# CanController.net
KiCad netlist of a schematic drawn in Altium Designer
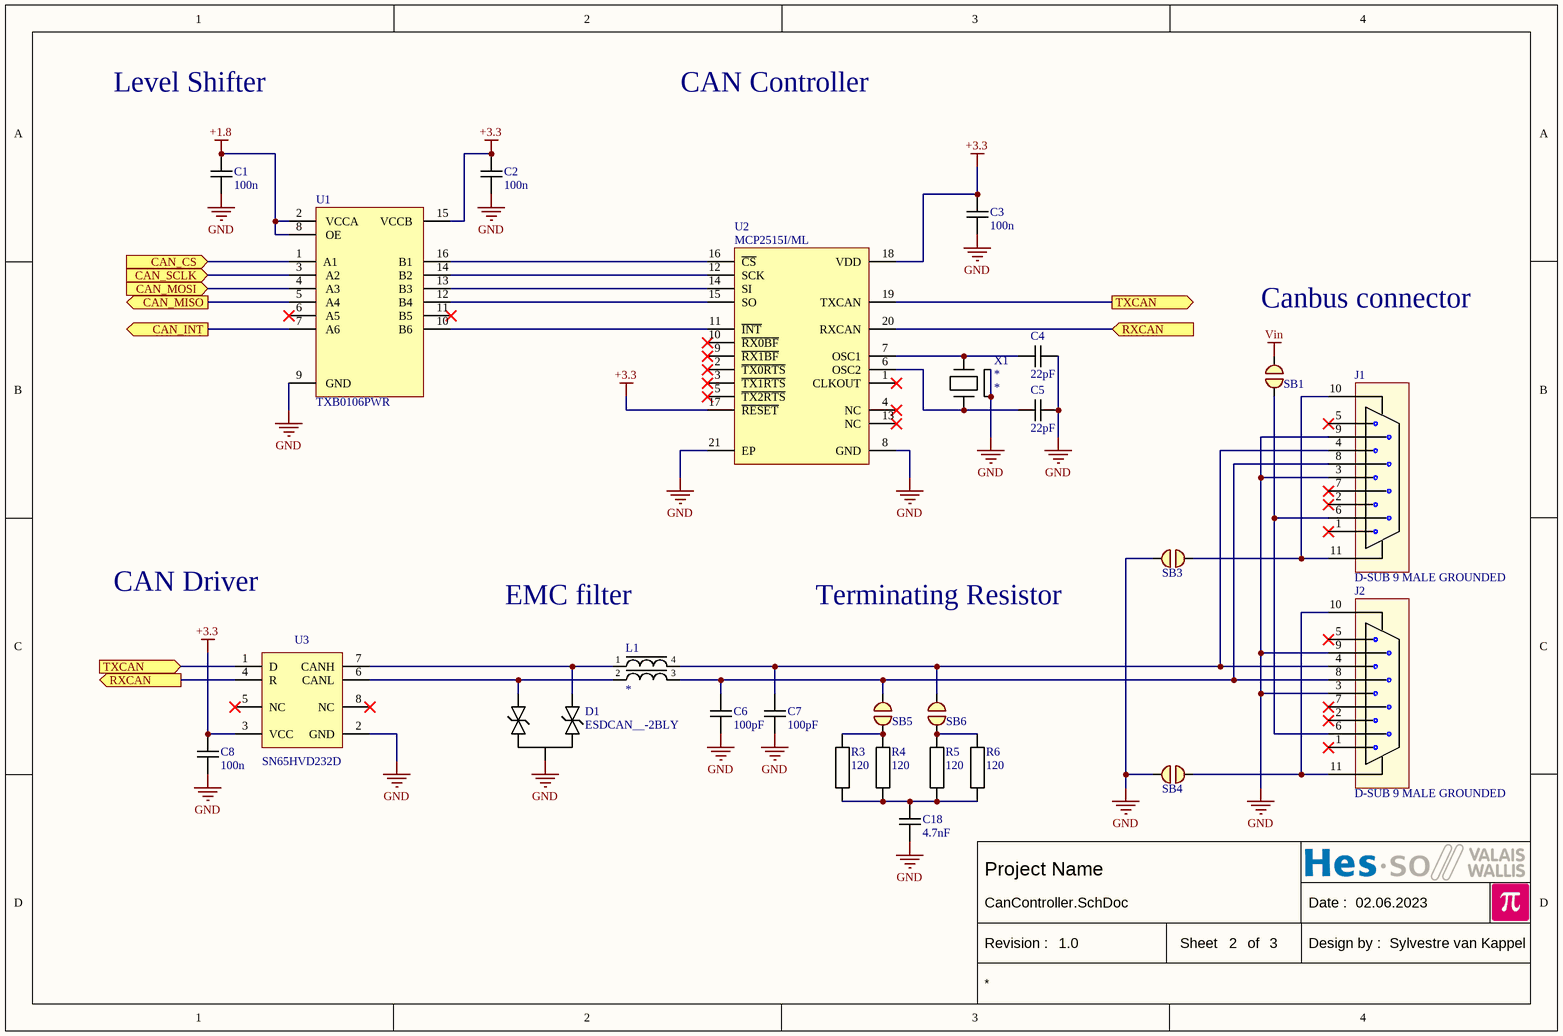
[diagram p0: CanController.SchDoc]

(export (version "E")
  (design (tool "Eeschema 10.0.6"))
  (components
    (comp (ref "C1")
      (value "100n")
      (footprint "CAPACITOR 1608 REFLOW")
      (description "Capacitor")
      (libsource (lib "Capacitor") (part "Capacitor"))
    )
    (comp (ref "C2")
      (value "100n")
      (footprint "CAPACITOR 1608 REFLOW")
      (description "Capacitor")
      (libsource (lib "Capacitor") (part "Capacitor"))
    )
    (comp (ref "C3")
      (value "100n")
      (footprint "CAPACITOR 1608 REFLOW")
      (description "Capacitor")
      (libsource (lib "Capacitor") (part "Capacitor"))
    )
    (comp (ref "C4")
      (value "22pF")
      (footprint "CAPACITOR 1608 REFLOW")
      (description "Capacitor")
      (libsource (lib "Capacitor") (part "Capacitor"))
    )
    (comp (ref "C5")
      (value "22pF")
      (footprint "CAPACITOR 1608 REFLOW")
      (description "Capacitor")
      (libsource (lib "Capacitor") (part "Capacitor"))
    )
    (comp (ref "C6")
      (value "100pF")
      (footprint "CAPACITOR 1608 REFLOW")
      (description "Capacitor")
      (libsource (lib "Capacitor") (part "Capacitor"))
    )
    (comp (ref "C7")
      (value "100pF")
      (footprint "CAPACITOR 1608 REFLOW")
      (description "Capacitor")
      (libsource (lib "Capacitor") (part "Capacitor"))
    )
    (comp (ref "C8")
      (value "100n")
      (footprint "CAPACITOR 1608 REFLOW")
      (description "Capacitor")
      (libsource (lib "Capacitor") (part "Capacitor"))
    )
    (comp (ref "C18")
      (value "4.7nF")
      (footprint "CAPACITOR 1608 REFLOW")
      (description "Capacitor")
      (libsource (lib "Capacitor") (part "Capacitor"))
    )
    (comp (ref "D1")
      (value "ESDCAN__-2BLY")
      (footprint "SOT23 P0.95 C1.6x3.0 H1.3")
      (description "Automotive dual-line TVS diode")
      (libsource (lib "Diode") (part "Diode ESDCAN__-2BLY"))
    )
    (comp (ref "J1")
      (value "D-SUB 9 MALE GROUNDED")
      (footprint "D-SUB 9 MALE ANGLE")
      (description "D-Subminiature 9 way Plug Right Angle")
      (libsource (lib "Connector") (part "D-SUB 9 MALE GROUNDED"))
    )
    (comp (ref "J2")
      (value "D-SUB 9 MALE GROUNDED")
      (footprint "D-SUB 9 MALE ANGLE")
      (description "D-Subminiature 9 way Plug Right Angle")
      (libsource (lib "Connector") (part "D-SUB 9 MALE GROUNDED"))
    )
    (comp (ref "L1")
      (value "*")
      (footprint "L CM 2X B82793C EPCOS")
      (description "Inductor Common Mode Filter")
      (libsource (lib "Inductor") (part "L CM 2X B82793C0 EPCOS"))
    )
    (comp (ref "R3")
      (value "120")
      (footprint "RESISTOR 1608 REFLOW")
      (description "Resistor")
      (libsource (lib "Resistor") (part "Resistor"))
    )
    (comp (ref "R4")
      (value "120")
      (footprint "RESISTOR 1608 REFLOW")
      (description "Resistor")
      (libsource (lib "Resistor") (part "Resistor"))
    )
    (comp (ref "R5")
      (value "120")
      (footprint "RESISTOR 1608 REFLOW")
      (description "Resistor")
      (libsource (lib "Resistor") (part "Resistor"))
    )
    (comp (ref "R6")
      (value "120")
      (footprint "RESISTOR 1608 REFLOW")
      (description "Resistor")
      (libsource (lib "Resistor") (part "Resistor"))
    )
    (comp (ref "SB1")
      (value "*")
      (footprint "Solder Bridge 1mm Unconnected")
      (description "Solderbridge Unconnected")
      (libsource (lib "Jumper") (part "Solderbridge Unconnected"))
    )
    (comp (ref "SB3")
      (value "*")
      (footprint "Solder Bridge 1mm Unconnected")
      (description "Solderbridge Unconnected")
      (libsource (lib "Jumper") (part "Solderbridge Unconnected"))
    )
    (comp (ref "SB4")
      (value "*")
      (footprint "Solder Bridge 1mm Unconnected")
      (description "Solderbridge Unconnected")
      (libsource (lib "Jumper") (part "Solderbridge Unconnected"))
    )
    (comp (ref "SB5")
      (value "*")
      (footprint "Solder Bridge 1mm Unconnected")
      (description "Solderbridge Unconnected")
      (libsource (lib "Jumper") (part "Solderbridge Unconnected"))
    )
    (comp (ref "SB6")
      (value "*")
      (footprint "Solder Bridge 1mm Unconnected")
      (description "Solderbridge Unconnected")
      (libsource (lib "Jumper") (part "Solderbridge Unconnected"))
    )
    (comp (ref "U1")
      (value "TXB0106PWR")
      (footprint "TSSOP16 P0.65 C5.0x4.5 H1.1")
      (libsource (lib "IntegratedCircuit") (part "TXB0106PWR"))
    )
    (comp (ref "U2")
      (value "MCP2515I/ML")
      (footprint "QFN20 P0.5 T2.05x2.05 C4.0x4.0 H0.85")
      (description "Stand-Alone CAN Controller with SPI Interface")
      (libsource (lib "IntegratedCircuit") (part "MCP2515I/ML"))
    )
    (comp (ref "U3")
      (value "SN65HVD232D")
      (footprint "SO8 P1.27 C4.0X5.0 H1.75")
      (description "CAN Bus Transceiver 3V3")
      (libsource (lib "IntegratedCircuit") (part "SN65HVD232D"))
    )
    (comp (ref "X1")
      (value "*")
      (footprint "CRYSTAL C3.2x2.5 Kyocera CX3225SB")
      (description "Crystal C3.2x2.5 Kyocera CX3225SB")
      (fields (field (name "ALTIUM_VALUE") "*"))
      (libsource (lib "Oscillator") (part "Crystal C3.2x2.5 Kyocera CX3225SB"))
    )
  )
  (nets
    (net (code "1") (name "+1.8") (class "Default")
      (node (ref "C1") (pin "2") (pinfunction "2_2") (pintype "passive"))
      (node (ref "U1") (pin "2") (pinfunction "VCCA_2") (pintype "passive"))
      (node (ref "U1") (pin "8") (pinfunction "OE_8") (pintype "passive"))
    )
    (net (code "2") (name "+3.3") (class "Default")
      (node (ref "C2") (pin "2") (pinfunction "2_2") (pintype "passive"))
      (node (ref "C3") (pin "2") (pinfunction "2_2") (pintype "passive"))
      (node (ref "C8") (pin "2") (pinfunction "2_2") (pintype "passive"))
      (node (ref "U1") (pin "15") (pinfunction "VCCB_15") (pintype "passive"))
      (node (ref "U2") (pin "17") (pinfunction "~{RESET}_17") (pintype "passive"))
      (node (ref "U2") (pin "18") (pinfunction "VDD_18") (pintype "passive"))
      (node (ref "U3") (pin "3") (pinfunction "VCC_3") (pintype "passive"))
    )
    (net (code "3") (name "/CAN_CS") (class "Default")
      (node (ref "U1") (pin "1") (pinfunction "A1_1") (pintype "passive"))
    )
    (net (code "4") (name "/CAN_INT") (class "Default")
      (node (ref "U1") (pin "7") (pinfunction "A6_7") (pintype "passive"))
    )
    (net (code "5") (name "/CAN_MISO") (class "Default")
      (node (ref "U1") (pin "5") (pinfunction "A4_5") (pintype "passive"))
    )
    (net (code "6") (name "/CAN_MOSI") (class "Default")
      (node (ref "U1") (pin "4") (pinfunction "A3_4") (pintype "passive"))
    )
    (net (code "7") (name "/CAN_SCLK") (class "Default")
      (node (ref "U1") (pin "3") (pinfunction "A2_3") (pintype "passive"))
    )
    (net (code "8") (name "/RXCAN") (class "Default")
      (node (ref "U2") (pin "20") (pinfunction "RXCAN_20") (pintype "passive"))
      (node (ref "U3") (pin "4") (pinfunction "R_4") (pintype "passive"))
    )
    (net (code "9") (name "/TXCAN") (class "Default")
      (node (ref "U2") (pin "19") (pinfunction "TXCAN_19") (pintype "passive"))
      (node (ref "U3") (pin "1") (pinfunction "D_1") (pintype "passive"))
    )
    (net (code "10") (name "GND") (class "Default")
      (node (ref "C1") (pin "1") (pinfunction "1_1") (pintype "passive"))
      (node (ref "C18") (pin "1") (pinfunction "1_1") (pintype "passive"))
      (node (ref "C2") (pin "1") (pinfunction "1_1") (pintype "passive"))
      (node (ref "C3") (pin "1") (pinfunction "1_1") (pintype "passive"))
      (node (ref "C4") (pin "1") (pinfunction "1_1") (pintype "passive"))
      (node (ref "C5") (pin "1") (pinfunction "1_1") (pintype "passive"))
      (node (ref "C6") (pin "1") (pinfunction "1_1") (pintype "passive"))
      (node (ref "C7") (pin "1") (pinfunction "1_1") (pintype "passive"))
      (node (ref "C8") (pin "1") (pinfunction "1_1") (pintype "passive"))
      (node (ref "D1") (pin "3") (pinfunction "COM_3") (pintype "passive"))
      (node (ref "J1") (pin "3") (pintype "passive"))
      (node (ref "J1") (pin "9") (pintype "passive"))
      (node (ref "J2") (pin "3") (pintype "passive"))
      (node (ref "J2") (pin "9") (pintype "passive"))
      (node (ref "SB3") (pin "1") (pinfunction "0_1") (pintype "passive"))
      (node (ref "SB4") (pin "1") (pinfunction "0_1") (pintype "passive"))
      (node (ref "U1") (pin "9") (pinfunction "GND_9") (pintype "passive"))
      (node (ref "U2") (pin "21") (pinfunction "EP_21") (pintype "passive"))
      (node (ref "U2") (pin "8") (pinfunction "GND_8") (pintype "passive"))
      (node (ref "U3") (pin "2") (pinfunction "GND_2") (pintype "passive"))
      (node (ref "X1") (pin "2") (pinfunction "2_2") (pintype "passive"))
      (node (ref "X1") (pin "4") (pinfunction "4_4") (pintype "passive"))
    )
    (net (code "11") (name "Net-(C18-Pad2)") (class "Default")
      (node (ref "C18") (pin "2") (pinfunction "2_2") (pintype "passive"))
      (node (ref "R3") (pin "1") (pinfunction "1_1") (pintype "passive"))
      (node (ref "R4") (pin "1") (pinfunction "1_1") (pintype "passive"))
      (node (ref "R5") (pin "1") (pinfunction "1_1") (pintype "passive"))
      (node (ref "R6") (pin "1") (pinfunction "1_1") (pintype "passive"))
    )
    (net (code "12") (name "Net-(D1-A1)") (class "Default")
      (node (ref "D1") (pin "1") (pinfunction "A1_1") (pintype "passive"))
      (node (ref "L1") (pin "1") (pinfunction "1_1") (pintype "passive"))
      (node (ref "U3") (pin "7") (pinfunction "CANH_7") (pintype "passive"))
    )
    (net (code "13") (name "Net-(D1-C2)") (class "Default")
      (node (ref "D1") (pin "2") (pinfunction "C2_2") (pintype "passive"))
      (node (ref "L1") (pin "2") (pinfunction "2_2") (pintype "passive"))
      (node (ref "U3") (pin "6") (pinfunction "CANL_6") (pintype "passive"))
    )
    (net (code "14") (name "Net-(SB1-1)") (class "Default")
      (node (ref "J1") (pin "6") (pintype "passive"))
      (node (ref "J2") (pin "6") (pintype "passive"))
      (node (ref "SB1") (pin "2") (pinfunction "1_2") (pintype "passive"))
    )
    (net (code "15") (name "Net-(SB3-1)") (class "Default")
      (node (ref "J1") (pin "10") (pintype "passive"))
      (node (ref "J1") (pin "11") (pintype "passive"))
      (node (ref "SB3") (pin "2") (pinfunction "1_2") (pintype "passive"))
    )
    (net (code "16") (name "Net-(SB4-1)") (class "Default")
      (node (ref "J2") (pin "10") (pintype "passive"))
      (node (ref "J2") (pin "11") (pintype "passive"))
      (node (ref "SB4") (pin "2") (pinfunction "1_2") (pintype "passive"))
    )
    (net (code "17") (name "Net-(SB5-0)") (class "Default")
      (node (ref "R3") (pin "2") (pinfunction "2_2") (pintype "passive"))
      (node (ref "R4") (pin "2") (pinfunction "2_2") (pintype "passive"))
      (node (ref "SB5") (pin "1") (pinfunction "0_1") (pintype "passive"))
    )
    (net (code "18") (name "Net-(SB5-1)") (class "Default")
      (node (ref "C6") (pin "2") (pinfunction "2_2") (pintype "passive"))
      (node (ref "J1") (pin "8") (pintype "passive"))
      (node (ref "J2") (pin "8") (pintype "passive"))
      (node (ref "L1") (pin "3") (pinfunction "3_3") (pintype "passive"))
      (node (ref "SB5") (pin "2") (pinfunction "1_2") (pintype "passive"))
    )
    (net (code "19") (name "Net-(SB6-0)") (class "Default")
      (node (ref "R5") (pin "2") (pinfunction "2_2") (pintype "passive"))
      (node (ref "R6") (pin "2") (pinfunction "2_2") (pintype "passive"))
      (node (ref "SB6") (pin "1") (pinfunction "0_1") (pintype "passive"))
    )
    (net (code "20") (name "Net-(SB6-1)") (class "Default")
      (node (ref "C7") (pin "2") (pinfunction "2_2") (pintype "passive"))
      (node (ref "J1") (pin "4") (pintype "passive"))
      (node (ref "J2") (pin "4") (pintype "passive"))
      (node (ref "L1") (pin "4") (pinfunction "4_4") (pintype "passive"))
      (node (ref "SB6") (pin "2") (pinfunction "1_2") (pintype "passive"))
    )
    (net (code "21") (name "Net-(U1-B1)") (class "Default")
      (node (ref "U1") (pin "16") (pinfunction "B1_16") (pintype "passive"))
      (node (ref "U2") (pin "16") (pinfunction "~{CS}_16") (pintype "passive"))
    )
    (net (code "22") (name "Net-(U1-B2)") (class "Default")
      (node (ref "U1") (pin "14") (pinfunction "B2_14") (pintype "passive"))
      (node (ref "U2") (pin "12") (pinfunction "SCK_12") (pintype "passive"))
    )
    (net (code "23") (name "Net-(U1-B3)") (class "Default")
      (node (ref "U1") (pin "13") (pinfunction "B3_13") (pintype "passive"))
      (node (ref "U2") (pin "14") (pinfunction "SI_14") (pintype "passive"))
    )
    (net (code "24") (name "Net-(U1-B4)") (class "Default")
      (node (ref "U1") (pin "12") (pinfunction "B4_12") (pintype "passive"))
      (node (ref "U2") (pin "15") (pinfunction "SO_15") (pintype "passive"))
    )
    (net (code "25") (name "Net-(U1-B6)") (class "Default")
      (node (ref "U1") (pin "10") (pinfunction "B6_10") (pintype "passive"))
      (node (ref "U2") (pin "11") (pinfunction "~{INT}_11") (pintype "passive"))
    )
    (net (code "26") (name "Net-(U2-OSC1)") (class "Default")
      (node (ref "C4") (pin "2") (pinfunction "2_2") (pintype "passive"))
      (node (ref "U2") (pin "7") (pinfunction "OSC1_7") (pintype "passive"))
      (node (ref "X1") (pin "3") (pinfunction "3_3") (pintype "passive"))
    )
    (net (code "27") (name "Net-(U2-OSC2)") (class "Default")
      (node (ref "C5") (pin "2") (pinfunction "2_2") (pintype "passive"))
      (node (ref "U2") (pin "6") (pinfunction "OSC2_6") (pintype "passive"))
      (node (ref "X1") (pin "1") (pinfunction "1_1") (pintype "passive"))
    )
    (net (code "28") (name "Vin") (class "Default")
      (node (ref "SB1") (pin "1") (pinfunction "0_1") (pintype "passive"))
    )
    (net (code "29") (name "unconnected-(J1-Pad1)") (class "Default")
      (node (ref "J1") (pin "1") (pintype "passive+no_connect"))
    )
    (net (code "30") (name "unconnected-(J1-Pad2)") (class "Default")
      (node (ref "J1") (pin "2") (pintype "passive+no_connect"))
    )
    (net (code "31") (name "unconnected-(J1-Pad5)") (class "Default")
      (node (ref "J1") (pin "5") (pintype "passive+no_connect"))
    )
    (net (code "32") (name "unconnected-(J1-Pad7)") (class "Default")
      (node (ref "J1") (pin "7") (pintype "passive+no_connect"))
    )
    (net (code "33") (name "unconnected-(J2-Pad1)") (class "Default")
      (node (ref "J2") (pin "1") (pintype "passive+no_connect"))
    )
    (net (code "34") (name "unconnected-(J2-Pad2)") (class "Default")
      (node (ref "J2") (pin "2") (pintype "passive+no_connect"))
    )
    (net (code "35") (name "unconnected-(J2-Pad5)") (class "Default")
      (node (ref "J2") (pin "5") (pintype "passive+no_connect"))
    )
    (net (code "36") (name "unconnected-(J2-Pad7)") (class "Default")
      (node (ref "J2") (pin "7") (pintype "passive+no_connect"))
    )
    (net (code "37") (name "unconnected-(U1-A5-Pad6)") (class "Default")
      (node (ref "U1") (pin "6") (pinfunction "A5_6") (pintype "passive+no_connect"))
    )
    (net (code "38") (name "unconnected-(U1-B5-Pad11)") (class "Default")
      (node (ref "U1") (pin "11") (pinfunction "B5_11") (pintype "passive+no_connect"))
    )
    (net (code "39") (name "unconnected-(U2-CLKOUT-Pad1)") (class "Default")
      (node (ref "U2") (pin "1") (pinfunction "CLKOUT_1") (pintype "passive+no_connect"))
    )
    (net (code "40") (name "unconnected-(U2-NC-Pad4)") (class "Default")
      (node (ref "U2") (pin "4") (pinfunction "NC_4") (pintype "passive+no_connect"))
    )
    (net (code "41") (name "unconnected-(U2-NC-Pad13)") (class "Default")
      (node (ref "U2") (pin "13") (pinfunction "NC_13") (pintype "passive+no_connect"))
    )
    (net (code "42") (name "unconnected-(U2-~{RX0BF}-Pad10)") (class "Default")
      (node (ref "U2") (pin "10") (pinfunction "~{RX0BF}_10") (pintype "passive+no_connect"))
    )
    (net (code "43") (name "unconnected-(U2-~{RX1BF}-Pad9)") (class "Default")
      (node (ref "U2") (pin "9") (pinfunction "~{RX1BF}_9") (pintype "passive+no_connect"))
    )
    (net (code "44") (name "unconnected-(U2-~{TX0RTS}-Pad2)") (class "Default")
      (node (ref "U2") (pin "2") (pinfunction "~{TX0RTS}_2") (pintype "passive+no_connect"))
    )
    (net (code "45") (name "unconnected-(U2-~{TX1RTS}-Pad3)") (class "Default")
      (node (ref "U2") (pin "3") (pinfunction "~{TX1RTS}_3") (pintype "passive+no_connect"))
    )
    (net (code "46") (name "unconnected-(U2-~{TX2RTS}-Pad5)") (class "Default")
      (node (ref "U2") (pin "5") (pinfunction "~{TX2RTS}_5") (pintype "passive+no_connect"))
    )
    (net (code "47") (name "unconnected-(U3-NC-Pad5)") (class "Default")
      (node (ref "U3") (pin "5") (pinfunction "NC_5") (pintype "passive+no_connect"))
    )
    (net (code "48") (name "unconnected-(U3-NC-Pad8)") (class "Default")
      (node (ref "U3") (pin "8") (pinfunction "NC_8") (pintype "passive+no_connect"))
    )
  )
)
